# max485.net
KiCad netlist of a schematic drawn in Altium Designer
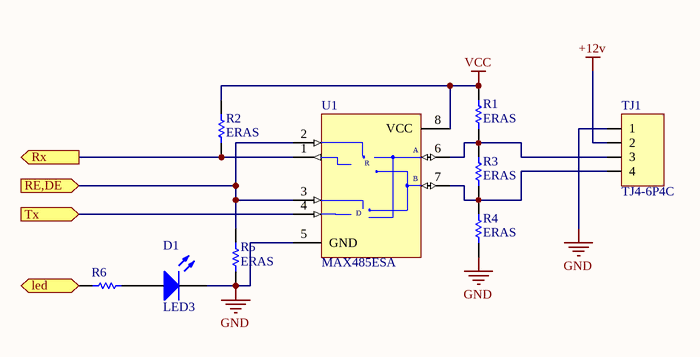
[diagram p0: max485.SchDoc]

(export (version "E")
  (design (tool "Eeschema 10.0.6"))
  (components
    (comp (ref "D1")
      (value "LED3")
      (footprint "3.5X2.8X1.9")
      (description "Typical BLUE SiC LED")
      (fields (field (name "PUBLISHER") "Altium Limited"))
      (libsource (lib "Miscellaneous Devices") (part "LED3"))
    )
    (comp (ref "R1")
      (value "ERAS")
      (footprint "ERA-0805")
      (fields (field (name "PUBLISHER") "Altium Limited"))
      (libsource (lib "Panasonic Resistor") (part "ERAS"))
    )
    (comp (ref "R2")
      (value "ERAS")
      (footprint "ERA-0805")
      (fields (field (name "PUBLISHER") "Altium Limited"))
      (libsource (lib "Panasonic Resistor") (part "ERAS"))
    )
    (comp (ref "R3")
      (value "ERAS")
      (footprint "ERA-0805")
      (fields (field (name "PUBLISHER") "Altium Limited"))
      (libsource (lib "Panasonic Resistor") (part "ERAS"))
    )
    (comp (ref "R4")
      (value "ERAS")
      (footprint "ERA-0805")
      (fields (field (name "PUBLISHER") "Altium Limited"))
      (libsource (lib "Panasonic Resistor") (part "ERAS"))
    )
    (comp (ref "R5")
      (value "ERAS")
      (footprint "ERA-0805")
      (fields (field (name "PUBLISHER") "Altium Limited"))
      (libsource (lib "Panasonic Resistor") (part "ERAS"))
    )
    (comp (ref "R6")
      (value "ERAS")
      (footprint "ERA-0805")
      (fields (field (name "PUBLISHER") "Altium Limited"))
      (libsource (lib "Panasonic Resistor") (part "ERAS"))
    )
    (comp (ref "TJ1") (value "TJ4-6P4C") (footprint "TJ4-6P4C") (libsource (lib "FAS") (part "TJ4-6P4C")))
    (comp (ref "U1")
      (value "MAX485ESA")
      (footprint "NSO8_N")
      (description "Low-Power, Slew-Rate-Limited RS-485/RS-422 Transceiver")
      (fields (field (name "PUBLISHER") "Altium Limited"))
      (libsource (lib "Maxim Communication Transceiver") (part "MAX485ESA"))
    )
  )
  (nets
    (net (code "1") (name "+12v") (class "Default")
      (node (ref "TJ1") (pin "2") (pinfunction "2_2") (pintype "passive"))
    )
    (net (code "2") (name "/RE,DE") (class "Default")
      (node (ref "R5") (pin "1") (pinfunction "1_1") (pintype "passive"))
      (node (ref "U1") (pin "2") (pinfunction "~{RE}_2") (pintype "input"))
      (node (ref "U1") (pin "3") (pinfunction "DE_3") (pintype "input"))
    )
    (net (code "3") (name "/Rx") (class "Default")
      (node (ref "R2") (pin "2") (pinfunction "2_2") (pintype "passive"))
      (node (ref "U1") (pin "1") (pinfunction "RO_1") (pintype "output"))
    )
    (net (code "4") (name "/Tx") (class "Default")
      (node (ref "U1") (pin "4") (pinfunction "DI_4") (pintype "input"))
    )
    (net (code "5") (name "/led") (class "Default")
      (node (ref "R6") (pin "1") (pinfunction "1_1") (pintype "passive"))
    )
    (net (code "6") (name "GND") (class "Default")
      (node (ref "D1") (pin "2") (pinfunction "K_2") (pintype "passive"))
      (node (ref "R4") (pin "2") (pinfunction "2_2") (pintype "passive"))
      (node (ref "R5") (pin "2") (pinfunction "2_2") (pintype "passive"))
      (node (ref "TJ1") (pin "1") (pinfunction "1_1") (pintype "passive"))
      (node (ref "U1") (pin "5") (pinfunction "GND_5") (pintype "power_in"))
    )
    (net (code "7") (name "Net-(D1-A)") (class "Default")
      (node (ref "D1") (pin "1") (pinfunction "A_1") (pintype "passive"))
      (node (ref "R6") (pin "2") (pinfunction "2_2") (pintype "passive"))
    )
    (net (code "8") (name "Net-(U1-A)") (class "Default")
      (node (ref "R1") (pin "2") (pinfunction "2_2") (pintype "passive"))
      (node (ref "R3") (pin "1") (pinfunction "1_1") (pintype "passive"))
      (node (ref "TJ1") (pin "3") (pinfunction "3_3") (pintype "passive"))
      (node (ref "U1") (pin "6") (pinfunction "A_6") (pintype "bidirectional"))
    )
    (net (code "9") (name "Net-(U1-B)") (class "Default")
      (node (ref "R3") (pin "2") (pinfunction "2_2") (pintype "passive"))
      (node (ref "R4") (pin "1") (pinfunction "1_1") (pintype "passive"))
      (node (ref "TJ1") (pin "4") (pinfunction "4_4") (pintype "passive"))
      (node (ref "U1") (pin "7") (pinfunction "B_7") (pintype "bidirectional"))
    )
    (net (code "10") (name "VCC") (class "Default")
      (node (ref "R1") (pin "1") (pinfunction "1_1") (pintype "passive"))
      (node (ref "R2") (pin "1") (pinfunction "1_1") (pintype "passive"))
      (node (ref "U1") (pin "8") (pinfunction "VCC_8") (pintype "power_in"))
    )
  )
)
